# User_Interface.net
KiCad netlist of a schematic drawn in EAGLE
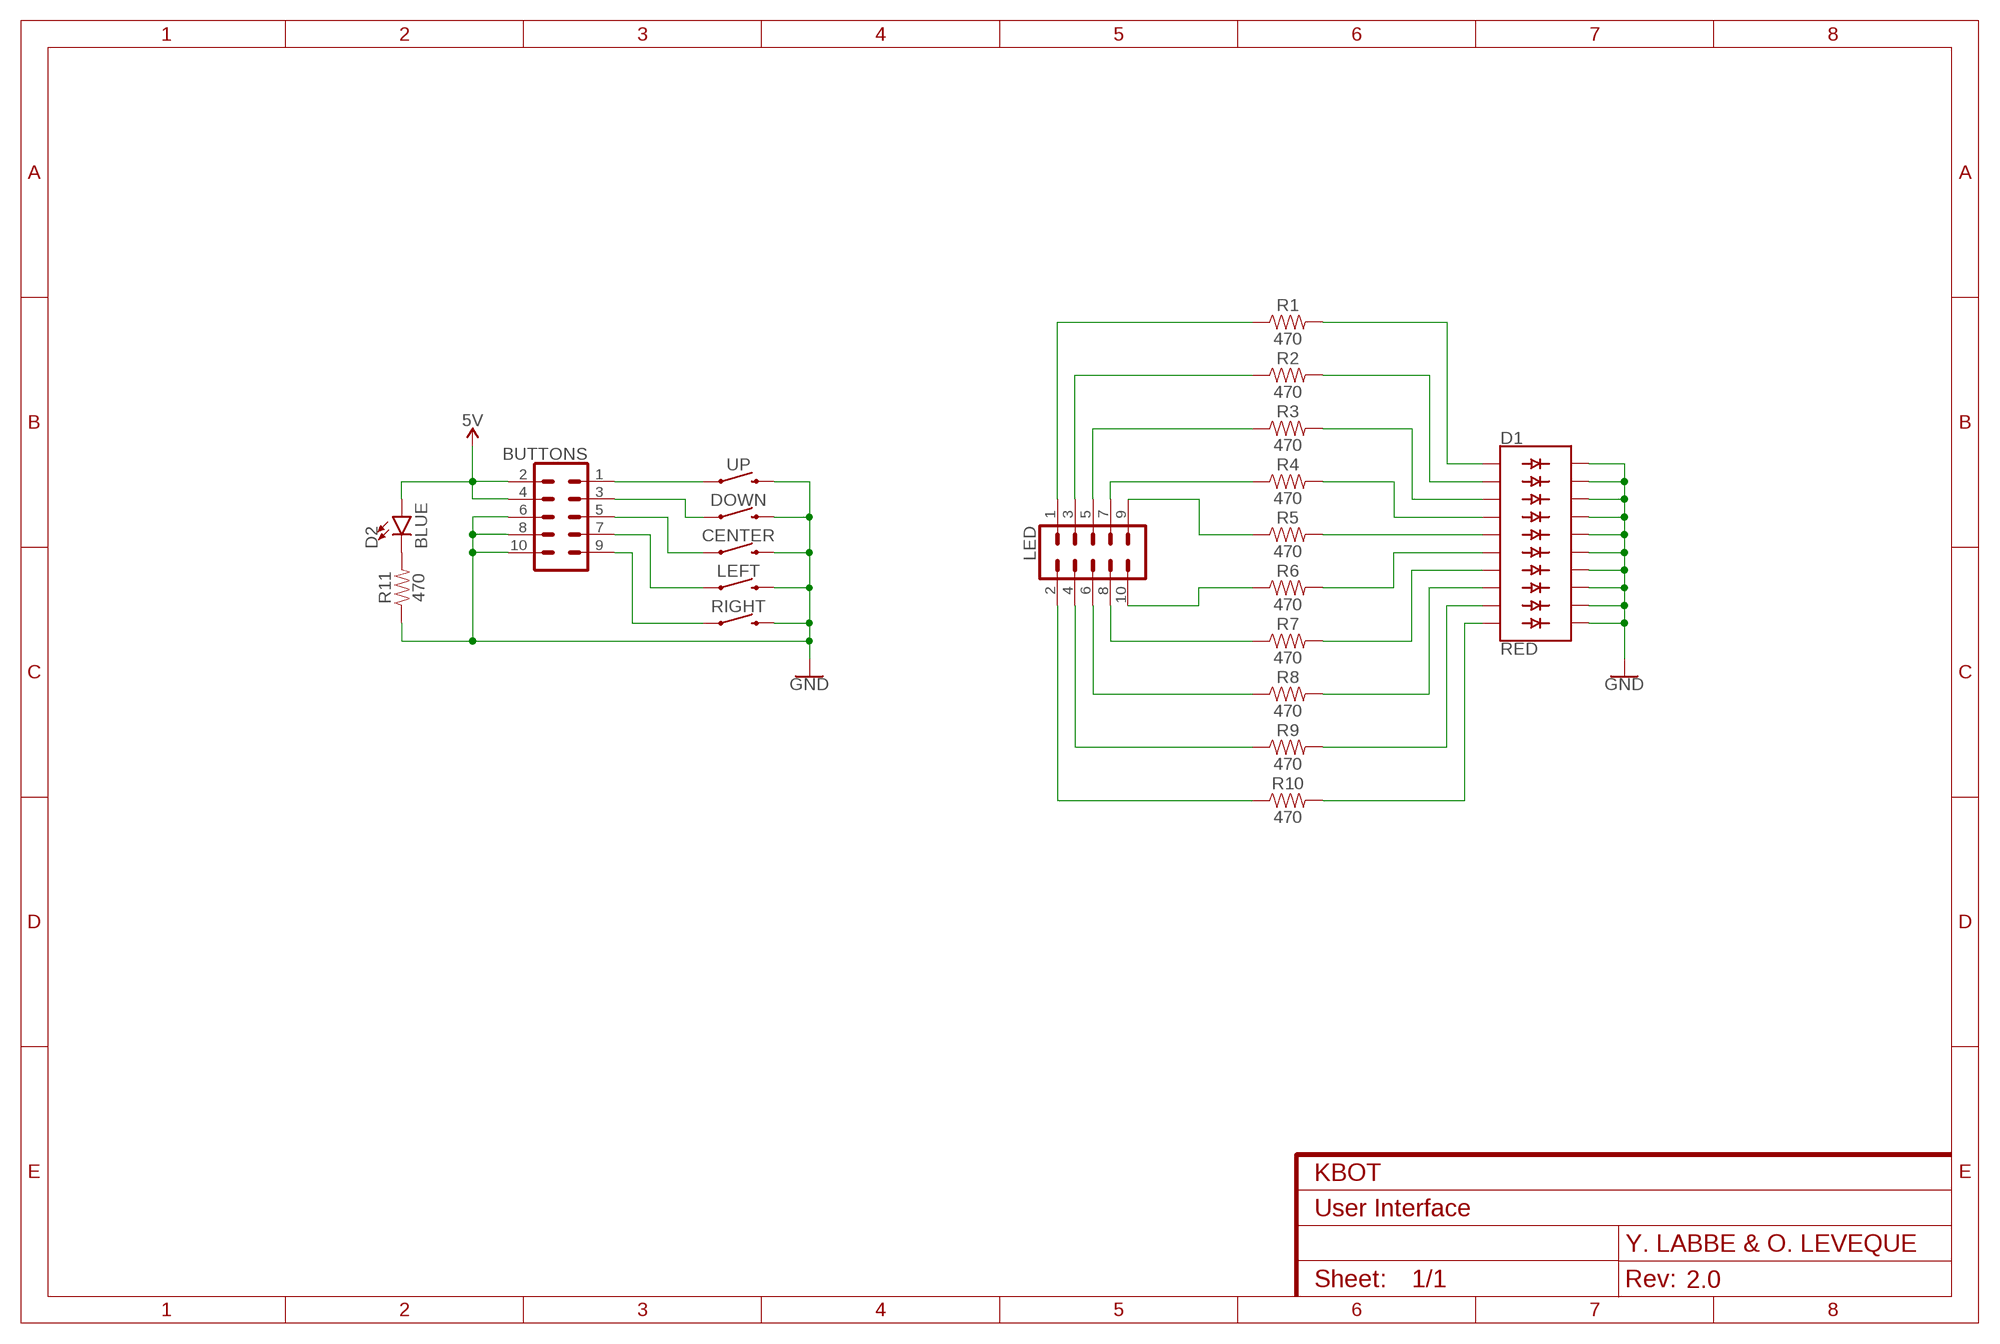
[diagram p0: schematic, sheet 1]

(export (version "E")
  (design (tool "Eeschema 10.0.6"))
  (components
    (comp (ref "BUTTONS")
      (value "CONN_05X2SHD")
      (footprint "eagle-import:2X5-SHROUDED")
      (libsource (lib "eagle-import") (part "CONN_05X2SHD"))
    )
    (comp (ref "CENTER")
      (value "MOMENTARY-SWITCH-SPST-PTH-6.0MM")
      (footprint "eagle-import:TACTILE_SWITCH_PTH_6.0MM")
      (libsource (lib "eagle-import") (part "MOMENTARY-SWITCH-SPST-PTH-6.0MM"))
    )
    (comp (ref "D1")
      (value "RED")
      (footprint "eagle-import:LED_BARGRAPH_10")
      (libsource (lib "eagle-import") (part "LED_BARGRAPH_10RED"))
    )
    (comp (ref "D2")
      (value "BLUE")
      (footprint "eagle-import:LED-1206")
      (libsource (lib "eagle-import") (part "LED-BLUE1206"))
    )
    (comp (ref "DOWN")
      (value "MOMENTARY-SWITCH-SPST-PTH-6.0MM")
      (footprint "eagle-import:TACTILE_SWITCH_PTH_6.0MM")
      (libsource (lib "eagle-import") (part "MOMENTARY-SWITCH-SPST-PTH-6.0MM"))
    )
    (comp (ref "LED")
      (value "CONN_05X2SHD")
      (footprint "eagle-import:2X5-SHROUDED")
      (libsource (lib "eagle-import") (part "CONN_05X2SHD"))
    )
    (comp (ref "LEFT")
      (value "MOMENTARY-SWITCH-SPST-PTH-6.0MM")
      (footprint "eagle-import:TACTILE_SWITCH_PTH_6.0MM")
      (libsource (lib "eagle-import") (part "MOMENTARY-SWITCH-SPST-PTH-6.0MM"))
    )
    (comp (ref "R1")
      (value "470")
      (footprint "eagle-import:1206")
      (libsource (lib "eagle-import") (part "RESISTOR1206"))
    )
    (comp (ref "R2")
      (value "470")
      (footprint "eagle-import:1206")
      (libsource (lib "eagle-import") (part "RESISTOR1206"))
    )
    (comp (ref "R3")
      (value "470")
      (footprint "eagle-import:1206")
      (libsource (lib "eagle-import") (part "RESISTOR1206"))
    )
    (comp (ref "R4")
      (value "470")
      (footprint "eagle-import:1206")
      (libsource (lib "eagle-import") (part "RESISTOR1206"))
    )
    (comp (ref "R5")
      (value "470")
      (footprint "eagle-import:1206")
      (libsource (lib "eagle-import") (part "RESISTOR1206"))
    )
    (comp (ref "R6")
      (value "470")
      (footprint "eagle-import:1206")
      (libsource (lib "eagle-import") (part "RESISTOR1206"))
    )
    (comp (ref "R7")
      (value "470")
      (footprint "eagle-import:1206")
      (libsource (lib "eagle-import") (part "RESISTOR1206"))
    )
    (comp (ref "R8")
      (value "470")
      (footprint "eagle-import:1206")
      (libsource (lib "eagle-import") (part "RESISTOR1206"))
    )
    (comp (ref "R9")
      (value "470")
      (footprint "eagle-import:1206")
      (libsource (lib "eagle-import") (part "RESISTOR1206"))
    )
    (comp (ref "R10")
      (value "470")
      (footprint "eagle-import:1206")
      (libsource (lib "eagle-import") (part "RESISTOR1206"))
    )
    (comp (ref "R11")
      (value "470")
      (footprint "eagle-import:1206")
      (libsource (lib "eagle-import") (part "RESISTOR1206"))
    )
    (comp (ref "RIGHT")
      (value "MOMENTARY-SWITCH-SPST-PTH-6.0MM")
      (footprint "eagle-import:TACTILE_SWITCH_PTH_6.0MM")
      (libsource (lib "eagle-import") (part "MOMENTARY-SWITCH-SPST-PTH-6.0MM"))
    )
    (comp (ref "UP")
      (value "MOMENTARY-SWITCH-SPST-PTH-6.0MM")
      (footprint "eagle-import:TACTILE_SWITCH_PTH_6.0MM")
      (libsource (lib "eagle-import") (part "MOMENTARY-SWITCH-SPST-PTH-6.0MM"))
    )
  )
  (nets
    (net (code "1") (name "5V") (class "Default")
      (node (ref "BUTTONS") (pin "2") (pinfunction "2_2") (pintype "passive"))
      (node (ref "BUTTONS") (pin "4") (pinfunction "4_4") (pintype "passive"))
      (node (ref "D2") (pin "A") (pinfunction "A_A") (pintype "passive"))
    )
    (net (code "2") (name "GND") (class "Default")
      (node (ref "BUTTONS") (pin "10") (pinfunction "10_10") (pintype "passive"))
      (node (ref "BUTTONS") (pin "6") (pinfunction "6_6") (pintype "passive"))
      (node (ref "BUTTONS") (pin "8") (pinfunction "8_8") (pintype "passive"))
      (node (ref "CENTER") (pin "3") (pinfunction "2_3") (pintype "passive"))
      (node (ref "D1") (pin "11") (pinfunction "C9_11") (pintype "passive"))
      (node (ref "D1") (pin "12") (pinfunction "C8_12") (pintype "passive"))
      (node (ref "D1") (pin "13") (pinfunction "C7_13") (pintype "passive"))
      (node (ref "D1") (pin "14") (pinfunction "C6_14") (pintype "passive"))
      (node (ref "D1") (pin "15") (pinfunction "C5_15") (pintype "passive"))
      (node (ref "D1") (pin "16") (pinfunction "C4_16") (pintype "passive"))
      (node (ref "D1") (pin "17") (pinfunction "C3_17") (pintype "passive"))
      (node (ref "D1") (pin "18") (pinfunction "C2_18") (pintype "passive"))
      (node (ref "D1") (pin "19") (pinfunction "C1_19") (pintype "passive"))
      (node (ref "D1") (pin "20") (pinfunction "C_20") (pintype "passive"))
      (node (ref "DOWN") (pin "3") (pinfunction "2_3") (pintype "passive"))
      (node (ref "LEFT") (pin "3") (pinfunction "2_3") (pintype "passive"))
      (node (ref "R11") (pin "1") (pinfunction "1_1") (pintype "passive"))
      (node (ref "RIGHT") (pin "3") (pinfunction "2_3") (pintype "passive"))
      (node (ref "UP") (pin "3") (pinfunction "2_3") (pintype "passive"))
    )
    (net (code "3") (name "Net-(BUTTONS-Pad1)") (class "Default")
      (node (ref "BUTTONS") (pin "1") (pinfunction "1_1") (pintype "passive"))
      (node (ref "UP") (pin "1") (pinfunction "1_1") (pintype "passive"))
    )
    (net (code "4") (name "Net-(BUTTONS-Pad3)") (class "Default")
      (node (ref "BUTTONS") (pin "3") (pinfunction "3_3") (pintype "passive"))
      (node (ref "DOWN") (pin "1") (pinfunction "1_1") (pintype "passive"))
    )
    (net (code "5") (name "Net-(BUTTONS-Pad5)") (class "Default")
      (node (ref "BUTTONS") (pin "5") (pinfunction "5_5") (pintype "passive"))
      (node (ref "CENTER") (pin "1") (pinfunction "1_1") (pintype "passive"))
    )
    (net (code "6") (name "Net-(BUTTONS-Pad7)") (class "Default")
      (node (ref "BUTTONS") (pin "7") (pinfunction "7_7") (pintype "passive"))
      (node (ref "LEFT") (pin "1") (pinfunction "1_1") (pintype "passive"))
    )
    (net (code "7") (name "Net-(BUTTONS-Pad9)") (class "Default")
      (node (ref "BUTTONS") (pin "9") (pinfunction "9_9") (pintype "passive"))
      (node (ref "RIGHT") (pin "1") (pinfunction "1_1") (pintype "passive"))
    )
    (net (code "8") (name "Net-(D1-A)") (class "Default")
      (node (ref "D1") (pin "1") (pinfunction "A_1") (pintype "passive"))
      (node (ref "R1") (pin "2") (pinfunction "2_2") (pintype "passive"))
    )
    (net (code "9") (name "Net-(D1-A1)") (class "Default")
      (node (ref "D1") (pin "2") (pinfunction "A1_2") (pintype "passive"))
      (node (ref "R2") (pin "2") (pinfunction "2_2") (pintype "passive"))
    )
    (net (code "10") (name "Net-(D1-A2)") (class "Default")
      (node (ref "D1") (pin "3") (pinfunction "A2_3") (pintype "passive"))
      (node (ref "R3") (pin "2") (pinfunction "2_2") (pintype "passive"))
    )
    (net (code "11") (name "Net-(D1-A3)") (class "Default")
      (node (ref "D1") (pin "4") (pinfunction "A3_4") (pintype "passive"))
      (node (ref "R4") (pin "2") (pinfunction "2_2") (pintype "passive"))
    )
    (net (code "12") (name "Net-(D1-A4)") (class "Default")
      (node (ref "D1") (pin "5") (pinfunction "A4_5") (pintype "passive"))
      (node (ref "R5") (pin "2") (pinfunction "2_2") (pintype "passive"))
    )
    (net (code "13") (name "Net-(D1-A5)") (class "Default")
      (node (ref "D1") (pin "6") (pinfunction "A5_6") (pintype "passive"))
      (node (ref "R6") (pin "2") (pinfunction "2_2") (pintype "passive"))
    )
    (net (code "14") (name "Net-(D1-A6)") (class "Default")
      (node (ref "D1") (pin "7") (pinfunction "A6_7") (pintype "passive"))
      (node (ref "R7") (pin "2") (pinfunction "2_2") (pintype "passive"))
    )
    (net (code "15") (name "Net-(D1-A7)") (class "Default")
      (node (ref "D1") (pin "8") (pinfunction "A7_8") (pintype "passive"))
      (node (ref "R8") (pin "2") (pinfunction "2_2") (pintype "passive"))
    )
    (net (code "16") (name "Net-(D1-A8)") (class "Default")
      (node (ref "D1") (pin "9") (pinfunction "A8_9") (pintype "passive"))
      (node (ref "R9") (pin "2") (pinfunction "2_2") (pintype "passive"))
    )
    (net (code "17") (name "Net-(D1-A9)") (class "Default")
      (node (ref "D1") (pin "10") (pinfunction "A9_10") (pintype "passive"))
      (node (ref "R10") (pin "2") (pinfunction "2_2") (pintype "passive"))
    )
    (net (code "18") (name "Net-(D2-PadC)") (class "Default")
      (node (ref "D2") (pin "C") (pinfunction "C_C") (pintype "passive"))
      (node (ref "R11") (pin "2") (pinfunction "2_2") (pintype "passive"))
    )
    (net (code "19") (name "Net-(LED-Pad1)") (class "Default")
      (node (ref "LED") (pin "1") (pinfunction "1_1") (pintype "passive"))
      (node (ref "R1") (pin "1") (pinfunction "1_1") (pintype "passive"))
    )
    (net (code "20") (name "Net-(LED-Pad2)") (class "Default")
      (node (ref "LED") (pin "2") (pinfunction "2_2") (pintype "passive"))
      (node (ref "R10") (pin "1") (pinfunction "1_1") (pintype "passive"))
    )
    (net (code "21") (name "Net-(LED-Pad3)") (class "Default")
      (node (ref "LED") (pin "3") (pinfunction "3_3") (pintype "passive"))
      (node (ref "R2") (pin "1") (pinfunction "1_1") (pintype "passive"))
    )
    (net (code "22") (name "Net-(LED-Pad4)") (class "Default")
      (node (ref "LED") (pin "4") (pinfunction "4_4") (pintype "passive"))
      (node (ref "R9") (pin "1") (pinfunction "1_1") (pintype "passive"))
    )
    (net (code "23") (name "Net-(LED-Pad5)") (class "Default")
      (node (ref "LED") (pin "5") (pinfunction "5_5") (pintype "passive"))
      (node (ref "R3") (pin "1") (pinfunction "1_1") (pintype "passive"))
    )
    (net (code "24") (name "Net-(LED-Pad6)") (class "Default")
      (node (ref "LED") (pin "6") (pinfunction "6_6") (pintype "passive"))
      (node (ref "R8") (pin "1") (pinfunction "1_1") (pintype "passive"))
    )
    (net (code "25") (name "Net-(LED-Pad7)") (class "Default")
      (node (ref "LED") (pin "7") (pinfunction "7_7") (pintype "passive"))
      (node (ref "R4") (pin "1") (pinfunction "1_1") (pintype "passive"))
    )
    (net (code "26") (name "Net-(LED-Pad8)") (class "Default")
      (node (ref "LED") (pin "8") (pinfunction "8_8") (pintype "passive"))
      (node (ref "R7") (pin "1") (pinfunction "1_1") (pintype "passive"))
    )
    (net (code "27") (name "Net-(LED-Pad9)") (class "Default")
      (node (ref "LED") (pin "9") (pinfunction "9_9") (pintype "passive"))
      (node (ref "R5") (pin "1") (pinfunction "1_1") (pintype "passive"))
    )
    (net (code "28") (name "Net-(LED-Pad10)") (class "Default")
      (node (ref "LED") (pin "10") (pinfunction "10_10") (pintype "passive"))
      (node (ref "R6") (pin "1") (pinfunction "1_1") (pintype "passive"))
    )
  )
)
